# 13_USB3_0_Connector3_4.net
KiCad netlist of a schematic drawn in Altium Designer
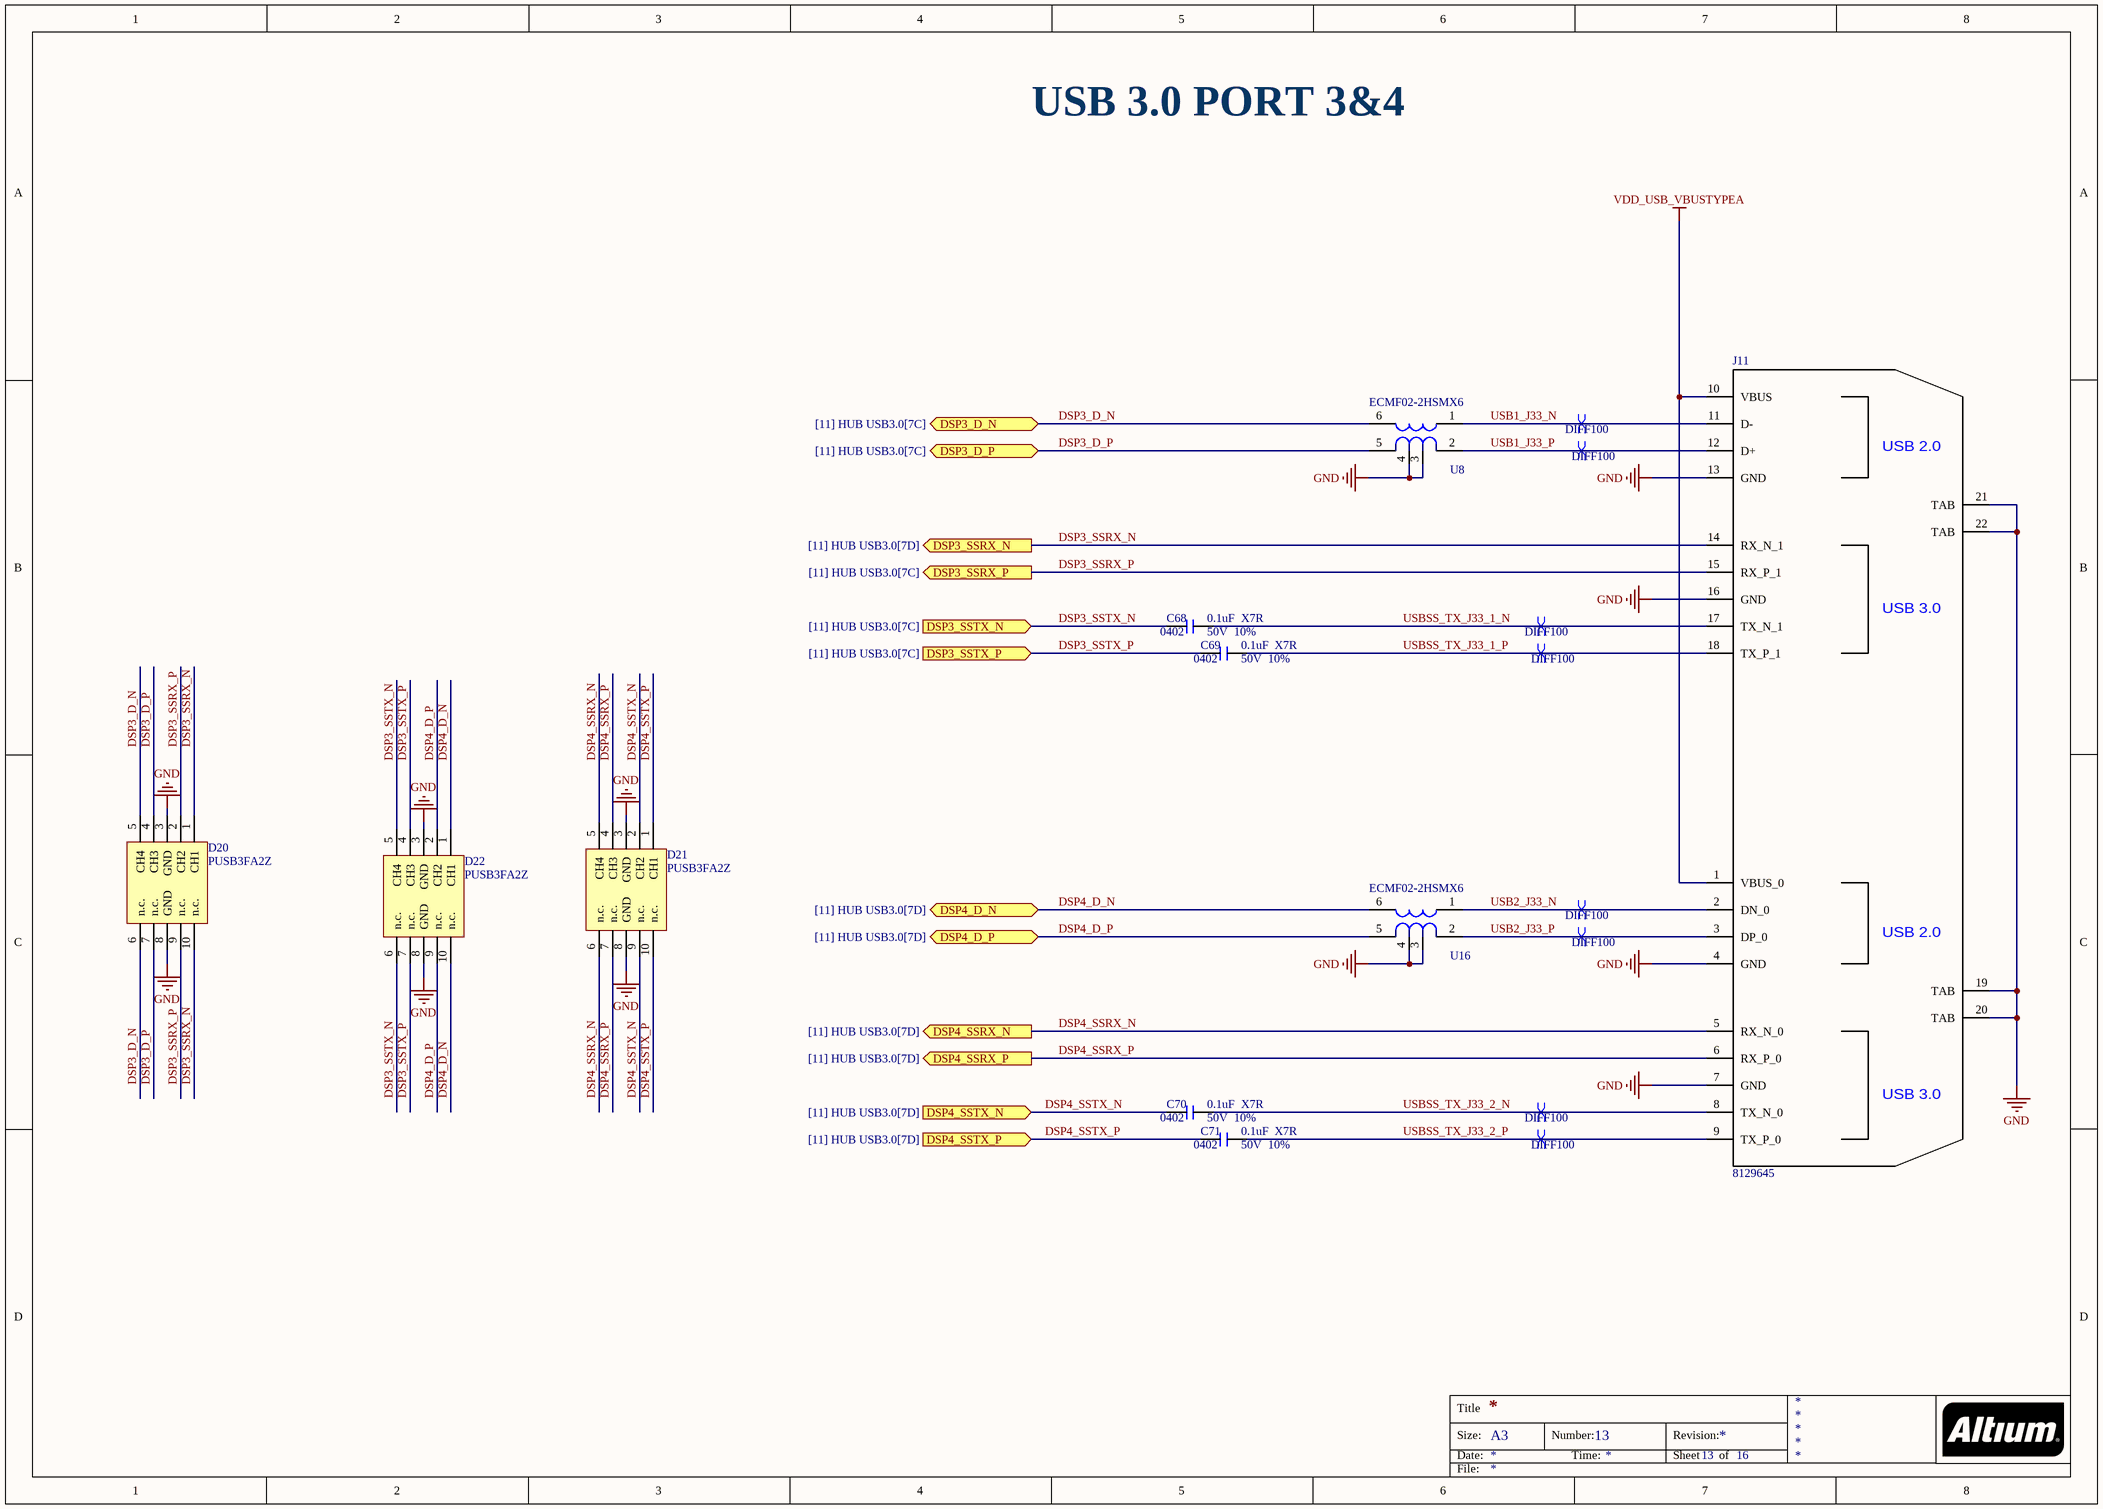
[diagram p0: [13] USB3.0_Connector3&4.SchDoc]

(export (version "E")
  (design (tool "Eeschema 10.0.6"))
  (components
    (comp (ref "C68")
      (value "0.1uF")
      (footprint "C0402M")
      (description "CAP CER 0.1UF 50V X7R 0402")
      (fields
        (field (name "MANUFACTURER") "Murata")
        (field (name "MANUFACTURER PART NUMBER") "GRM155R71H104KE14D")
        (field (name "CASE/PACKAGE") "0402")
        (field (name "TOLERANCE") "10%")
        (field (name "DIELECTRIC") "X7R")
        (field (name "VOLTAGE") "50V")
      )
      (libsource (lib "CommonLib") (part "CAP_CER"))
    )
    (comp (ref "C69")
      (value "0.1uF")
      (footprint "C0402M")
      (description "CAP CER 0.1UF 50V X7R 0402")
      (fields
        (field (name "MANUFACTURER") "Murata")
        (field (name "MANUFACTURER PART NUMBER") "GRM155R71H104KE14D")
        (field (name "CASE/PACKAGE") "0402")
        (field (name "TOLERANCE") "10%")
        (field (name "DIELECTRIC") "X7R")
        (field (name "VOLTAGE") "50V")
      )
      (libsource (lib "CommonLib") (part "CAP_CER"))
    )
    (comp (ref "C70")
      (value "0.1uF")
      (footprint "C0402M")
      (description "CAP CER 0.1UF 50V X7R 0402")
      (fields
        (field (name "MANUFACTURER") "Murata")
        (field (name "MANUFACTURER PART NUMBER") "GRM155R71H104KE14D")
        (field (name "CASE/PACKAGE") "0402")
        (field (name "TOLERANCE") "10%")
        (field (name "DIELECTRIC") "X7R")
        (field (name "VOLTAGE") "50V")
      )
      (libsource (lib "CommonLib") (part "CAP_CER"))
    )
    (comp (ref "C71")
      (value "0.1uF")
      (footprint "C0402M")
      (description "CAP CER 0.1UF 50V X7R 0402")
      (fields
        (field (name "MANUFACTURER") "Murata")
        (field (name "MANUFACTURER PART NUMBER") "GRM155R71H104KE14D")
        (field (name "CASE/PACKAGE") "0402")
        (field (name "TOLERANCE") "10%")
        (field (name "DIELECTRIC") "X7R")
        (field (name "VOLTAGE") "50V")
      )
      (libsource (lib "CommonLib") (part "CAP_CER"))
    )
    (comp (ref "D20")
      (value "PUSB3FA2Z")
      (footprint "SON50P100X50-10N")
      (description "ESD Suppressors / TVS Diodes PUSB3FA2 XSON10")
      (libsource (lib "Nauvus") (part "PUSB3FA2Z"))
    )
    (comp (ref "D21")
      (value "PUSB3FA2Z")
      (footprint "SON50P100X50-10N")
      (description "ESD Suppressors / TVS Diodes PUSB3FA2 XSON10")
      (libsource (lib "Nauvus") (part "PUSB3FA2Z"))
    )
    (comp (ref "D22")
      (value "PUSB3FA2Z")
      (footprint "SON50P100X50-10N")
      (description "ESD Suppressors / TVS Diodes PUSB3FA2 XSON10")
      (libsource (lib "Nauvus") (part "PUSB3FA2Z"))
    )
    (comp (ref "J11")
      (value "48406-0003")
      (footprint "Molex_48406-0003_0")
      (description "Conn USB 3.0 Type A F 18 POS 2mm/2.5mm Solder RA Thru-Hole 18 Terminal 2 Port USB 3.0 Tray")
      (fields (field (name "SUPPLIER PART NUMBER 1") "8129645"))
      (libsource (lib "Schlib1") (part "48406-0003"))
    )
    (comp (ref "U8")
      (value "ECMF02-2HSMX6")
      (footprint "SON50P150X55-6N")
      (description "CMC 200MA 2LN SMD ESD")
      (libsource (lib "Nauvus") (part "ECMF02-2AMX6"))
    )
    (comp (ref "U16")
      (value "ECMF02-2HSMX6")
      (footprint "SON50P150X55-6N")
      (description "CMC 200MA 2LN SMD ESD")
      (libsource (lib "Nauvus") (part "ECMF02-2AMX6"))
    )
  )
  (nets
    (net (code "1") (name "/DSP3_D_N") (class "Default")
      (node (ref "D20") (pin "5") (pinfunction "CH4_5") (pintype "passive"))
      (node (ref "D20") (pin "6") (pinfunction "n.c._6") (pintype "passive"))
      (node (ref "U8") (pin "6") (pinfunction "6_6") (pintype "passive"))
    )
    (net (code "2") (name "/DSP3_D_P") (class "Default")
      (node (ref "D20") (pin "4") (pinfunction "CH3_4") (pintype "passive"))
      (node (ref "D20") (pin "7") (pinfunction "n.c._7") (pintype "passive"))
      (node (ref "U8") (pin "5") (pinfunction "5_5") (pintype "passive"))
    )
    (net (code "3") (name "/DSP3_SSRX_N") (class "Default")
      (node (ref "D20") (pin "1") (pinfunction "CH1_1") (pintype "passive"))
      (node (ref "D20") (pin "10") (pinfunction "n.c._10") (pintype "passive"))
      (node (ref "J11") (pin "14") (pinfunction "RX_N_1_14") (pintype "passive"))
    )
    (net (code "4") (name "/DSP3_SSRX_P") (class "Default")
      (node (ref "D20") (pin "2") (pinfunction "CH2_2") (pintype "passive"))
      (node (ref "D20") (pin "9") (pinfunction "n.c._9") (pintype "passive"))
      (node (ref "J11") (pin "15") (pinfunction "RX_P_1_15") (pintype "passive"))
    )
    (net (code "5") (name "/DSP3_SSTX_N") (class "Default")
      (node (ref "C68") (pin "1") (pinfunction "1_1") (pintype "passive"))
      (node (ref "D22") (pin "5") (pinfunction "CH4_5") (pintype "passive"))
      (node (ref "D22") (pin "6") (pinfunction "n.c._6") (pintype "passive"))
    )
    (net (code "6") (name "/DSP3_SSTX_P") (class "Default")
      (node (ref "C69") (pin "1") (pinfunction "1_1") (pintype "passive"))
      (node (ref "D22") (pin "4") (pinfunction "CH3_4") (pintype "passive"))
      (node (ref "D22") (pin "7") (pinfunction "n.c._7") (pintype "passive"))
    )
    (net (code "7") (name "/DSP4_D_N") (class "Default")
      (node (ref "D22") (pin "1") (pinfunction "CH1_1") (pintype "passive"))
      (node (ref "D22") (pin "10") (pinfunction "n.c._10") (pintype "passive"))
      (node (ref "U16") (pin "6") (pinfunction "6_6") (pintype "passive"))
    )
    (net (code "8") (name "/DSP4_D_P") (class "Default")
      (node (ref "D22") (pin "2") (pinfunction "CH2_2") (pintype "passive"))
      (node (ref "D22") (pin "9") (pinfunction "n.c._9") (pintype "passive"))
      (node (ref "U16") (pin "5") (pinfunction "5_5") (pintype "passive"))
    )
    (net (code "9") (name "/DSP4_SSRX_N") (class "Default")
      (node (ref "D21") (pin "5") (pinfunction "CH4_5") (pintype "passive"))
      (node (ref "D21") (pin "6") (pinfunction "n.c._6") (pintype "passive"))
      (node (ref "J11") (pin "5") (pinfunction "RX_N_0_5") (pintype "passive"))
    )
    (net (code "10") (name "/DSP4_SSRX_P") (class "Default")
      (node (ref "D21") (pin "4") (pinfunction "CH3_4") (pintype "passive"))
      (node (ref "D21") (pin "7") (pinfunction "n.c._7") (pintype "passive"))
      (node (ref "J11") (pin "6") (pinfunction "RX_P_0_6") (pintype "passive"))
    )
    (net (code "11") (name "/DSP4_SSTX_N") (class "Default")
      (node (ref "C70") (pin "1") (pinfunction "1_1") (pintype "passive"))
      (node (ref "D21") (pin "2") (pinfunction "CH2_2") (pintype "passive"))
      (node (ref "D21") (pin "9") (pinfunction "n.c._9") (pintype "passive"))
    )
    (net (code "12") (name "/DSP4_SSTX_P") (class "Default")
      (node (ref "C71") (pin "1") (pinfunction "1_1") (pintype "passive"))
      (node (ref "D21") (pin "1") (pinfunction "CH1_1") (pintype "passive"))
      (node (ref "D21") (pin "10") (pinfunction "n.c._10") (pintype "passive"))
    )
    (net (code "13") (name "/USB1_J33_N") (class "Default")
      (node (ref "J11") (pin "11") (pinfunction "D-_11") (pintype "passive"))
      (node (ref "U8") (pin "1") (pinfunction "1_1") (pintype "passive"))
    )
    (net (code "14") (name "/USB1_J33_P") (class "Default")
      (node (ref "J11") (pin "12") (pinfunction "D+_12") (pintype "passive"))
      (node (ref "U8") (pin "2") (pinfunction "2_2") (pintype "passive"))
    )
    (net (code "15") (name "/USB2_J33_N") (class "Default")
      (node (ref "J11") (pin "2") (pinfunction "DN_0_2") (pintype "passive"))
      (node (ref "U16") (pin "1") (pinfunction "1_1") (pintype "passive"))
    )
    (net (code "16") (name "/USB2_J33_P") (class "Default")
      (node (ref "J11") (pin "3") (pinfunction "DP_0_3") (pintype "passive"))
      (node (ref "U16") (pin "2") (pinfunction "2_2") (pintype "passive"))
    )
    (net (code "17") (name "/USBSS_TX_J33_1_N") (class "Default")
      (node (ref "C68") (pin "2") (pinfunction "2_2") (pintype "passive"))
      (node (ref "J11") (pin "17") (pinfunction "TX_N_1_17") (pintype "passive"))
    )
    (net (code "18") (name "/USBSS_TX_J33_1_P") (class "Default")
      (node (ref "C69") (pin "2") (pinfunction "2_2") (pintype "passive"))
      (node (ref "J11") (pin "18") (pinfunction "TX_P_1_18") (pintype "passive"))
    )
    (net (code "19") (name "/USBSS_TX_J33_2_N") (class "Default")
      (node (ref "C70") (pin "2") (pinfunction "2_2") (pintype "passive"))
      (node (ref "J11") (pin "8") (pinfunction "TX_N_0_8") (pintype "passive"))
    )
    (net (code "20") (name "/USBSS_TX_J33_2_P") (class "Default")
      (node (ref "C71") (pin "2") (pinfunction "2_2") (pintype "passive"))
      (node (ref "J11") (pin "9") (pinfunction "TX_P_0_9") (pintype "passive"))
    )
    (net (code "21") (name "GND") (class "Default")
      (node (ref "D20") (pin "3") (pinfunction "GND_3") (pintype "passive"))
      (node (ref "D20") (pin "8") (pinfunction "GND_8") (pintype "passive"))
      (node (ref "D21") (pin "3") (pinfunction "GND_3") (pintype "passive"))
      (node (ref "D21") (pin "8") (pinfunction "GND_8") (pintype "passive"))
      (node (ref "D22") (pin "3") (pinfunction "GND_3") (pintype "passive"))
      (node (ref "D22") (pin "8") (pinfunction "GND_8") (pintype "passive"))
      (node (ref "J11") (pin "13") (pinfunction "GND_13") (pintype "power_in"))
      (node (ref "J11") (pin "16") (pinfunction "GND_16") (pintype "passive"))
      (node (ref "J11") (pin "19") (pinfunction "TAB_19") (pintype "passive"))
      (node (ref "J11") (pin "20") (pinfunction "TAB_20") (pintype "passive"))
      (node (ref "J11") (pin "21") (pinfunction "TAB_21") (pintype "passive"))
      (node (ref "J11") (pin "22") (pinfunction "TAB_22") (pintype "passive"))
      (node (ref "J11") (pin "4") (pinfunction "GND_4") (pintype "passive"))
      (node (ref "J11") (pin "7") (pinfunction "GND_7") (pintype "passive"))
      (node (ref "U16") (pin "3") (pinfunction "3_3") (pintype "passive"))
      (node (ref "U16") (pin "4") (pinfunction "4_4") (pintype "passive"))
      (node (ref "U8") (pin "3") (pinfunction "3_3") (pintype "passive"))
      (node (ref "U8") (pin "4") (pinfunction "4_4") (pintype "passive"))
    )
    (net (code "22") (name "VDD_USB_VBUSTYPEA") (class "Default")
      (node (ref "J11") (pin "1") (pinfunction "VBUS_0_1") (pintype "passive"))
      (node (ref "J11") (pin "10") (pinfunction "VBUS_10") (pintype "power_in"))
    )
  )
)
